# power_board.net
KiCad netlist of a schematic drawn in EAGLE
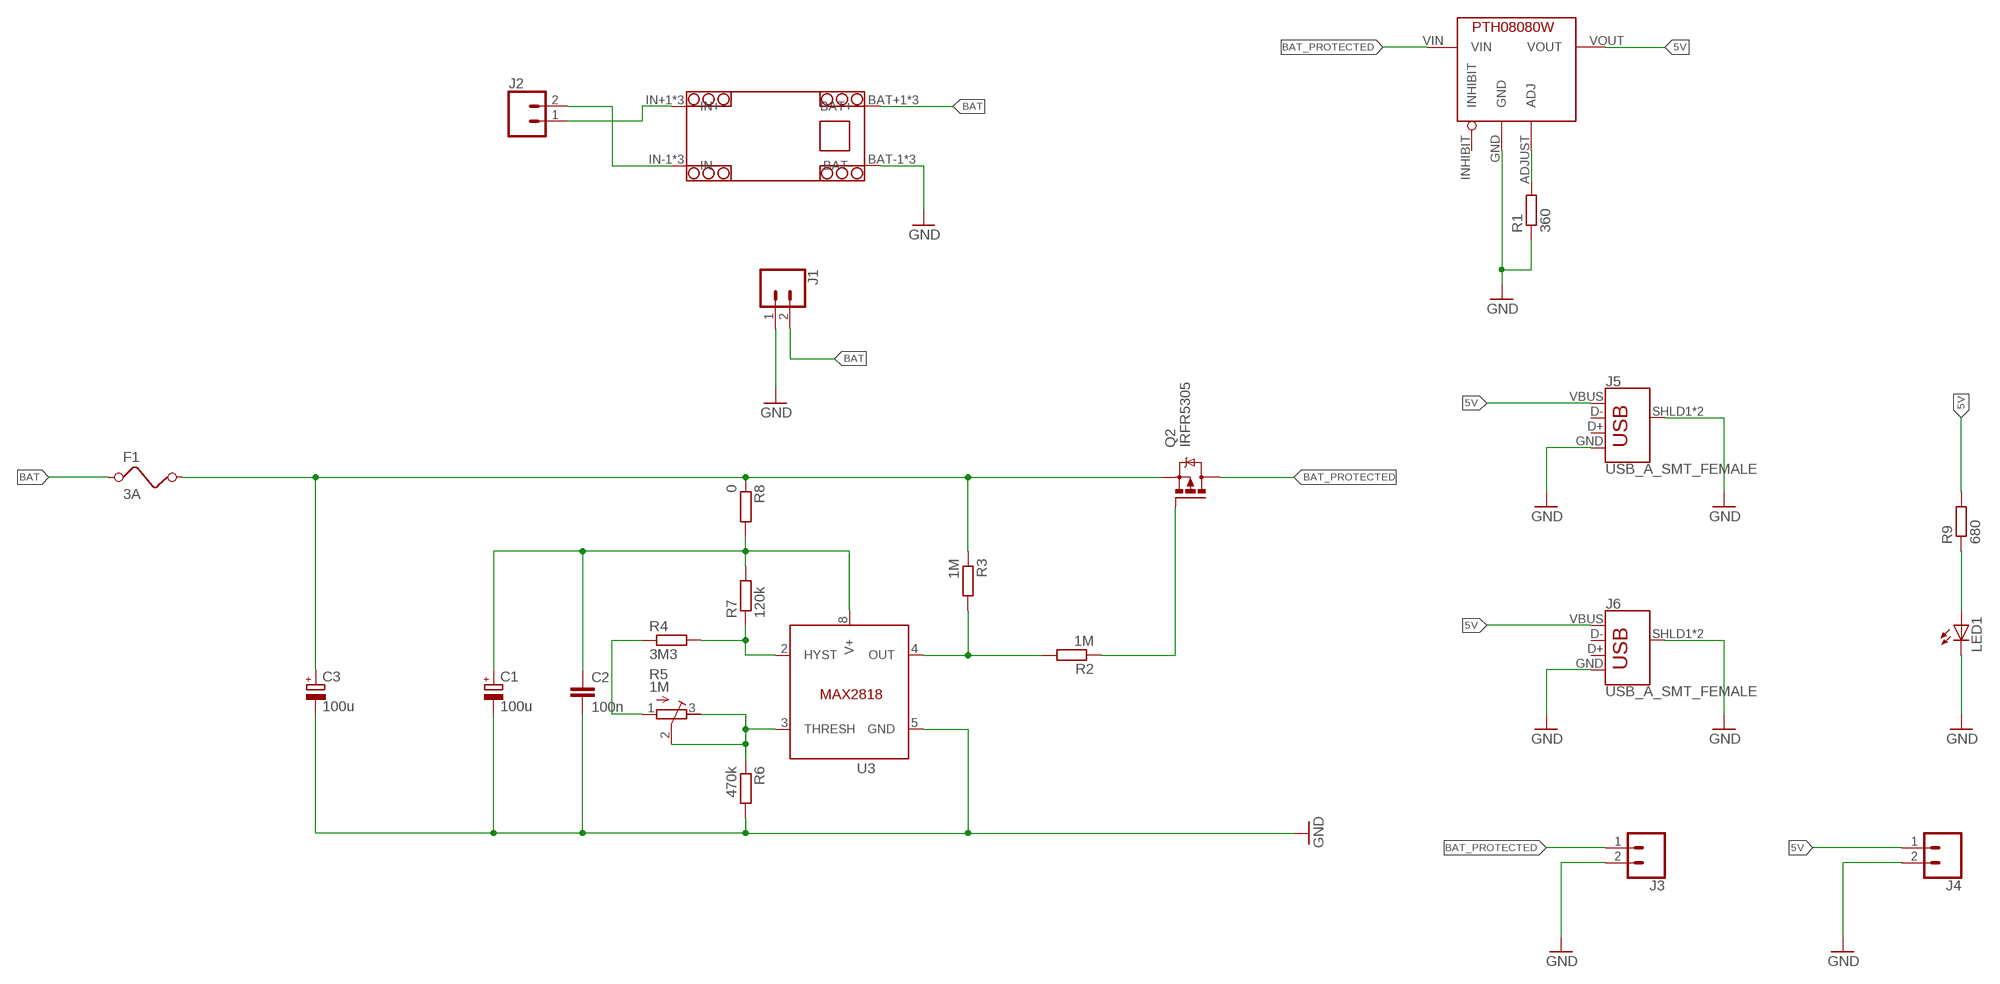
[diagram p0: schematic, sheet 1]

(export (version "E")
  (design (tool "Eeschema 10.0.6"))
  (components
    (comp (ref "C1")
      (value "100u")
      (footprint "eagle-import:E3,5-8")
      (libsource (lib "eagle-import") (part "CPOL-EUE3.5-8"))
    )
    (comp (ref "C2")
      (value "100n")
      (footprint "eagle-import:C1206")
      (libsource (lib "eagle-import") (part "C-EUC1206"))
    )
    (comp (ref "C3")
      (value "100u")
      (footprint "eagle-import:E3,5-8")
      (libsource (lib "eagle-import") (part "CPOL-EUE3.5-8"))
    )
    (comp (ref "F1")
      (value "3A")
      (footprint "eagle-import:FUSE")
      (libsource (lib "eagle-import") (part "FUSE"))
    )
    (comp (ref "J1")
      (value "CONN_025MM")
      (footprint "eagle-import:SCREWTERMINAL-5MM-2")
      (libsource (lib "eagle-import") (part "CONN_025MM"))
    )
    (comp (ref "J2")
      (value "CONN_025MM")
      (footprint "eagle-import:SCREWTERMINAL-5MM-2")
      (libsource (lib "eagle-import") (part "CONN_025MM"))
    )
    (comp (ref "J3")
      (value "CONN_02")
      (footprint "eagle-import:1X02")
      (libsource (lib "eagle-import") (part "CONN_02"))
    )
    (comp (ref "J4")
      (value "CONN_025MM")
      (footprint "eagle-import:SCREWTERMINAL-5MM-2")
      (libsource (lib "eagle-import") (part "CONN_025MM"))
    )
    (comp (ref "J5")
      (value "USB_A_SMT_FEMALE")
      (footprint "eagle-import:USB-A-S-SILK-FEMALE")
      (libsource (lib "eagle-import") (part "USB_A_SMT_FEMALE"))
    )
    (comp (ref "J6")
      (value "USB_A_SMT_FEMALE")
      (footprint "eagle-import:USB-A-S-SILK-FEMALE")
      (libsource (lib "eagle-import") (part "USB_A_SMT_FEMALE"))
    )
    (comp (ref "LED1")
      (value "LED3MM")
      (footprint "eagle-import:LED3MM")
      (libsource (lib "eagle-import") (part "LED3MM"))
    )
    (comp (ref "Q2")
      (value "IRFR5305")
      (footprint "eagle-import:D-PAK_TO252AA")
      (libsource (lib "eagle-import") (part "IRF?5305R"))
    )
    (comp (ref "R1")
      (value "360")
      (footprint "eagle-import:R1206")
      (libsource (lib "eagle-import") (part "R-EU_R1206"))
    )
    (comp (ref "R2")
      (value "1M")
      (footprint "eagle-import:R1206")
      (libsource (lib "eagle-import") (part "R-EU_R1206"))
    )
    (comp (ref "R3")
      (value "1M")
      (footprint "eagle-import:R1206")
      (libsource (lib "eagle-import") (part "R-EU_R1206"))
    )
    (comp (ref "R4")
      (value "3M3")
      (footprint "eagle-import:R1206")
      (libsource (lib "eagle-import") (part "R-EU_R1206"))
    )
    (comp (ref "R5")
      (value "1M")
      (footprint "eagle-import:RTRIM64Y")
      (libsource (lib "eagle-import") (part "R-TRIMM64Y"))
    )
    (comp (ref "R6")
      (value "470k")
      (footprint "eagle-import:R1206")
      (libsource (lib "eagle-import") (part "R-EU_R1206"))
    )
    (comp (ref "R7")
      (value "120k")
      (footprint "eagle-import:R1206")
      (libsource (lib "eagle-import") (part "R-EU_R1206"))
    )
    (comp (ref "R8")
      (value "0")
      (footprint "eagle-import:R1206")
      (libsource (lib "eagle-import") (part "R-EU_R1206"))
    )
    (comp (ref "R9")
      (value "680")
      (footprint "eagle-import:R1206")
      (libsource (lib "eagle-import") (part "R-EU_R1206"))
    )
    (comp (ref "U1")
      (value "YZXSTUDIO_SOLARCHARGERDEFAULT")
      (footprint "eagle-import:YZXSTUDIO_SOLARCHARGER")
      (libsource (lib "eagle-import") (part "YZXSTUDIO_SOLARCHARGERDEFAULT"))
    )
    (comp (ref "U2")
      (value "PTH08080WPTH08080W")
      (footprint "eagle-import:PTH08080W")
      (libsource (lib "eagle-import") (part "PTH08080WPTH08080W"))
    )
    (comp (ref "U3")
      (value "MAX2812MAX2812_SOIC8")
      (footprint "eagle-import:SOIC127P600X175-8N")
      (libsource (lib "eagle-import") (part "MAX2812MAX2812_SOIC8"))
    )
  )
  (nets
    (net (code "1") (name "5V") (class "Default")
      (node (ref "J4") (pin "1") (pinfunction "1_1") (pintype "passive"))
      (node (ref "J5") (pin "VBUS") (pinfunction "VBUS_VBUS") (pintype "power_in"))
      (node (ref "J6") (pin "VBUS") (pinfunction "VBUS_VBUS") (pintype "power_in"))
      (node (ref "R9") (pin "2") (pinfunction "2_2") (pintype "passive"))
      (node (ref "U2") (pin "VOUT") (pinfunction "VOUT_VOUT") (pintype "output"))
    )
    (net (code "2") (name "BAT") (class "Default")
      (node (ref "F1") (pin "1") (pinfunction "1_1") (pintype "passive"))
      (node (ref "J1") (pin "2") (pinfunction "2_2") (pintype "passive"))
      (node (ref "U1") (pin "BAT+1") (pinfunction "BAT+_BAT+1") (pintype "bidirectional"))
      (node (ref "U1") (pin "BAT+2") (pinfunction "BAT+_BAT+2") (pintype "bidirectional"))
      (node (ref "U1") (pin "BAT+3") (pinfunction "BAT+_BAT+3") (pintype "bidirectional"))
    )
    (net (code "3") (name "BAT_PROTECTED") (class "Default")
      (node (ref "J3") (pin "1") (pinfunction "1_1") (pintype "passive"))
      (node (ref "Q2") (pin "4") (pinfunction "D_4") (pintype "passive"))
      (node (ref "U2") (pin "VIN") (pinfunction "VIN_VIN") (pintype "input"))
    )
    (net (code "4") (name "GND") (class "Default")
      (node (ref "C1") (pin "-") (pinfunction "-_-") (pintype "passive"))
      (node (ref "C2") (pin "2") (pinfunction "2_2") (pintype "passive"))
      (node (ref "C3") (pin "-") (pinfunction "-_-") (pintype "passive"))
      (node (ref "J1") (pin "1") (pinfunction "1_1") (pintype "passive"))
      (node (ref "J3") (pin "2") (pinfunction "2_2") (pintype "passive"))
      (node (ref "J4") (pin "2") (pinfunction "2_2") (pintype "passive"))
      (node (ref "J5") (pin "GND") (pinfunction "GND_GND") (pintype "power_in"))
      (node (ref "J5") (pin "SHLD1") (pinfunction "SHIELD_SHLD1") (pintype "bidirectional"))
      (node (ref "J5") (pin "SHLD2") (pinfunction "SHIELD_SHLD2") (pintype "bidirectional"))
      (node (ref "J6") (pin "GND") (pinfunction "GND_GND") (pintype "power_in"))
      (node (ref "J6") (pin "SHLD1") (pinfunction "SHIELD_SHLD1") (pintype "bidirectional"))
      (node (ref "J6") (pin "SHLD2") (pinfunction "SHIELD_SHLD2") (pintype "bidirectional"))
      (node (ref "LED1") (pin "K") (pinfunction "C_K") (pintype "passive"))
      (node (ref "R1") (pin "1") (pinfunction "1_1") (pintype "passive"))
      (node (ref "R6") (pin "2") (pinfunction "2_2") (pintype "passive"))
      (node (ref "U1") (pin "BAT-1") (pinfunction "BAT-_BAT-1") (pintype "bidirectional"))
      (node (ref "U1") (pin "BAT-2") (pinfunction "BAT-_BAT-2") (pintype "bidirectional"))
      (node (ref "U1") (pin "BAT-3") (pinfunction "BAT-_BAT-3") (pintype "bidirectional"))
      (node (ref "U2") (pin "GND") (pinfunction "GND_GND") (pintype "power_in"))
      (node (ref "U3") (pin "5") (pinfunction "GND_5") (pintype "bidirectional"))
    )
    (net (code "5") (name "Net-(J2-Pad1)") (class "Default")
      (node (ref "J2") (pin "1") (pinfunction "1_1") (pintype "passive"))
      (node (ref "U1") (pin "IN+1") (pinfunction "IN+_IN+1") (pintype "bidirectional"))
      (node (ref "U1") (pin "IN+2") (pinfunction "IN+_IN+2") (pintype "bidirectional"))
      (node (ref "U1") (pin "IN+3") (pinfunction "IN+_IN+3") (pintype "bidirectional"))
    )
    (net (code "6") (name "Net-(J2-Pad2)") (class "Default")
      (node (ref "J2") (pin "2") (pinfunction "2_2") (pintype "passive"))
      (node (ref "U1") (pin "IN-1") (pinfunction "IN-_IN-1") (pintype "bidirectional"))
      (node (ref "U1") (pin "IN-2") (pinfunction "IN-_IN-2") (pintype "bidirectional"))
      (node (ref "U1") (pin "IN-3") (pinfunction "IN-_IN-3") (pintype "bidirectional"))
    )
    (net (code "7") (name "Net-(LED1-PadA)") (class "Default")
      (node (ref "LED1") (pin "A") (pinfunction "A_A") (pintype "passive"))
      (node (ref "R9") (pin "1") (pinfunction "1_1") (pintype "passive"))
    )
    (net (code "8") (name "Net-(Q2-G)") (class "Default")
      (node (ref "Q2") (pin "1") (pinfunction "G_1") (pintype "passive"))
      (node (ref "R2") (pin "1") (pinfunction "1_1") (pintype "passive"))
    )
    (net (code "9") (name "Net-(Q2-S)") (class "Default")
      (node (ref "C3") (pin "+") (pinfunction "+_+") (pintype "passive"))
      (node (ref "F1") (pin "2") (pinfunction "2_2") (pintype "passive"))
      (node (ref "Q2") (pin "3") (pinfunction "S_3") (pintype "passive"))
      (node (ref "R3") (pin "1") (pinfunction "1_1") (pintype "passive"))
      (node (ref "R8") (pin "1") (pinfunction "1_1") (pintype "passive"))
    )
    (net (code "10") (name "Net-(R5-A)") (class "Default")
      (node (ref "R4") (pin "1") (pinfunction "1_1") (pintype "passive"))
      (node (ref "R5") (pin "1") (pinfunction "A_1") (pintype "passive"))
    )
    (net (code "11") (name "Net-(R5-E)") (class "Default")
      (node (ref "R5") (pin "2") (pinfunction "S_2") (pintype "passive"))
      (node (ref "R5") (pin "3") (pinfunction "E_3") (pintype "passive"))
      (node (ref "R6") (pin "1") (pinfunction "1_1") (pintype "passive"))
      (node (ref "U3") (pin "3") (pinfunction "THRESH_3") (pintype "bidirectional"))
    )
    (net (code "12") (name "Net-(U2-ADJ)") (class "Default")
      (node (ref "R1") (pin "2") (pinfunction "2_2") (pintype "passive"))
      (node (ref "U2") (pin "ADJUST") (pinfunction "ADJ_ADJUST") (pintype "input"))
    )
    (net (code "13") (name "Net-(U3-HYST)") (class "Default")
      (node (ref "R4") (pin "2") (pinfunction "2_2") (pintype "passive"))
      (node (ref "R7") (pin "1") (pinfunction "1_1") (pintype "passive"))
      (node (ref "U3") (pin "2") (pinfunction "HYST_2") (pintype "bidirectional"))
    )
    (net (code "14") (name "Net-(U3-OUT)") (class "Default")
      (node (ref "R2") (pin "2") (pinfunction "2_2") (pintype "passive"))
      (node (ref "R3") (pin "2") (pinfunction "2_2") (pintype "passive"))
      (node (ref "U3") (pin "4") (pinfunction "OUT_4") (pintype "bidirectional"))
    )
    (net (code "15") (name "Net-(U3-V+)") (class "Default")
      (node (ref "C1") (pin "+") (pinfunction "+_+") (pintype "passive"))
      (node (ref "C2") (pin "1") (pinfunction "1_1") (pintype "passive"))
      (node (ref "R7") (pin "2") (pinfunction "2_2") (pintype "passive"))
      (node (ref "R8") (pin "2") (pinfunction "2_2") (pintype "passive"))
      (node (ref "U3") (pin "8") (pinfunction "V+_8") (pintype "bidirectional"))
    )
    (net (code "16") (name "unconnected-(J5-PadD+)") (class "Default")
      (node (ref "J5") (pin "D+") (pinfunction "D+_D+") (pintype "bidirectional"))
    )
    (net (code "17") (name "unconnected-(J5-PadD-)") (class "Default")
      (node (ref "J5") (pin "D-") (pinfunction "D-_D-") (pintype "bidirectional"))
    )
    (net (code "18") (name "unconnected-(J6-PadD+)") (class "Default")
      (node (ref "J6") (pin "D+") (pinfunction "D+_D+") (pintype "bidirectional"))
    )
    (net (code "19") (name "unconnected-(J6-PadD-)") (class "Default")
      (node (ref "J6") (pin "D-") (pinfunction "D-_D-") (pintype "bidirectional"))
    )
    (net (code "20") (name "unconnected-(U2-PadINHIBIT)") (class "Default")
      (node (ref "U2") (pin "INHIBIT") (pinfunction "INHIBIT_INHIBIT") (pintype "output"))
    )
  )
)
